# FADE.net
KiCad netlist of a schematic drawn in Altium Designer
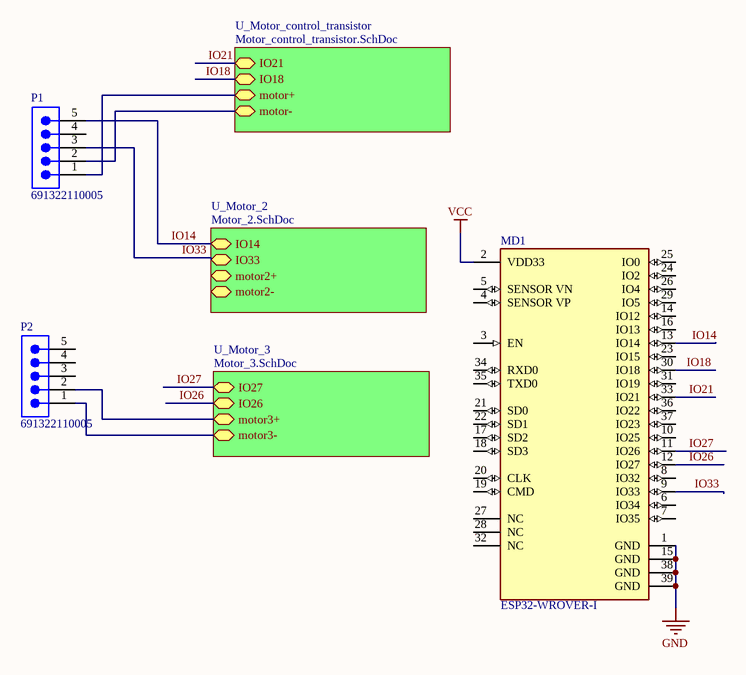
[diagram p0: FADE.SchDoc]

(export (version "E")
  (design (tool "Eeschema 10.0.6"))
  (components
    (comp (ref "MD1")
      (value "ESP32-WROVER-I")
      (footprint "FP-ESP32-WROVER-I-MFG")
      (description "SMD MODULE, ESP32-D0WDQ6, 32MBIT")
      (fields
        (field (name "MANUFACTURER") "Espressif")
        (field (name "OCTOPART") "https://octopart.com/esp32-wrover-i-espressif+systems-89171349")
      )
      (libsource (lib "Altium Content Vault") (part "cbbb37af8bcfe61dfd46ac9418f0340"))
    )
    (comp (ref "P1")
      (value "691322110005")
      (footprint "691322110005")
      (fields (field (name "VOLTAGE") "300V"))
      (libsource (lib "Altium Content Vault") (part "TBL - 1R - 05P - Male"))
    )
    (comp (ref "P2")
      (value "691322110005")
      (footprint "691322110005")
      (fields (field (name "VOLTAGE") "300V"))
      (libsource (lib "Altium Content Vault") (part "TBL - 1R - 05P - Male"))
    )
  )
  (nets
    (net (code "1") (name "/IO14") (class "Default")
      (node (ref "MD1") (pin "13") (pinfunction "IO14_13") (pintype "bidirectional"))
      (node (ref "P1") (pin "5") (pinfunction "5_5") (pintype "passive"))
    )
    (net (code "2") (name "/IO18") (class "Default")
      (node (ref "MD1") (pin "30") (pinfunction "IO18_30") (pintype "bidirectional"))
    )
    (net (code "3") (name "/IO21") (class "Default")
      (node (ref "MD1") (pin "33") (pinfunction "IO21_33") (pintype "bidirectional"))
    )
    (net (code "4") (name "/IO26") (class "Default")
      (node (ref "MD1") (pin "12") (pinfunction "IO27_12") (pintype "bidirectional"))
    )
    (net (code "5") (name "/IO27") (class "Default")
      (node (ref "MD1") (pin "11") (pinfunction "IO26_11") (pintype "bidirectional"))
    )
    (net (code "6") (name "/IO33") (class "Default")
      (node (ref "MD1") (pin "9") (pinfunction "IO33_9") (pintype "bidirectional"))
      (node (ref "P1") (pin "3") (pinfunction "3_3") (pintype "passive"))
    )
    (net (code "7") (name "/motor+") (class "Default")
      (node (ref "P1") (pin "1") (pinfunction "1_1") (pintype "passive"))
    )
    (net (code "8") (name "/motor-") (class "Default")
      (node (ref "P1") (pin "2") (pinfunction "2_2") (pintype "passive"))
    )
    (net (code "11") (name "/motor3+") (class "Default")
      (node (ref "P2") (pin "2") (pinfunction "2_2") (pintype "passive"))
    )
    (net (code "12") (name "/motor3-") (class "Default")
      (node (ref "P2") (pin "1") (pinfunction "1_1") (pintype "passive"))
    )
    (net (code "13") (name "GND") (class "Default")
      (node (ref "MD1") (pin "1") (pinfunction "GND_1") (pintype "power_in"))
      (node (ref "MD1") (pin "15") (pinfunction "GND_15") (pintype "power_in"))
      (node (ref "MD1") (pin "38") (pinfunction "GND_38") (pintype "power_in"))
      (node (ref "MD1") (pin "39") (pinfunction "GND_39") (pintype "power_in"))
    )
    (net (code "14") (name "VCC") (class "Default")
      (node (ref "MD1") (pin "2") (pinfunction "VDD33_2") (pintype "power_in"))
    )
    (net (code "15") (name "unconnected-(MD1-CLK-Pad20)") (class "Default")
      (node (ref "MD1") (pin "20") (pinfunction "CLK_20") (pintype "bidirectional"))
    )
    (net (code "16") (name "unconnected-(MD1-CMD-Pad19)") (class "Default")
      (node (ref "MD1") (pin "19") (pinfunction "CMD_19") (pintype "bidirectional"))
    )
    (net (code "17") (name "unconnected-(MD1-EN-Pad3)") (class "Default")
      (node (ref "MD1") (pin "3") (pinfunction "EN_3") (pintype "input"))
    )
    (net (code "18") (name "unconnected-(MD1-IO0-Pad25)") (class "Default")
      (node (ref "MD1") (pin "25") (pinfunction "IO0_25") (pintype "bidirectional"))
    )
    (net (code "19") (name "unconnected-(MD1-IO2-Pad24)") (class "Default")
      (node (ref "MD1") (pin "24") (pinfunction "IO2_24") (pintype "bidirectional"))
    )
    (net (code "20") (name "unconnected-(MD1-IO4-Pad26)") (class "Default")
      (node (ref "MD1") (pin "26") (pinfunction "IO4_26") (pintype "bidirectional"))
    )
    (net (code "21") (name "unconnected-(MD1-IO5-Pad29)") (class "Default")
      (node (ref "MD1") (pin "29") (pinfunction "IO5_29") (pintype "bidirectional"))
    )
    (net (code "22") (name "unconnected-(MD1-IO12-Pad14)") (class "Default")
      (node (ref "MD1") (pin "14") (pinfunction "IO12_14") (pintype "bidirectional"))
    )
    (net (code "23") (name "unconnected-(MD1-IO13-Pad16)") (class "Default")
      (node (ref "MD1") (pin "16") (pinfunction "IO13_16") (pintype "bidirectional"))
    )
    (net (code "24") (name "unconnected-(MD1-IO15-Pad23)") (class "Default")
      (node (ref "MD1") (pin "23") (pinfunction "IO15_23") (pintype "bidirectional"))
    )
    (net (code "25") (name "unconnected-(MD1-IO19-Pad31)") (class "Default")
      (node (ref "MD1") (pin "31") (pinfunction "IO19_31") (pintype "bidirectional"))
    )
    (net (code "26") (name "unconnected-(MD1-IO22-Pad36)") (class "Default")
      (node (ref "MD1") (pin "36") (pinfunction "IO22_36") (pintype "bidirectional"))
    )
    (net (code "27") (name "unconnected-(MD1-IO23-Pad37)") (class "Default")
      (node (ref "MD1") (pin "37") (pinfunction "IO23_37") (pintype "bidirectional"))
    )
    (net (code "28") (name "unconnected-(MD1-IO25-Pad10)") (class "Default")
      (node (ref "MD1") (pin "10") (pinfunction "IO25_10") (pintype "bidirectional"))
    )
    (net (code "29") (name "unconnected-(MD1-IO32-Pad8)") (class "Default")
      (node (ref "MD1") (pin "8") (pinfunction "IO32_8") (pintype "bidirectional"))
    )
    (net (code "30") (name "unconnected-(MD1-IO34-Pad6)") (class "Default")
      (node (ref "MD1") (pin "6") (pinfunction "IO34_6") (pintype "bidirectional"))
    )
    (net (code "31") (name "unconnected-(MD1-IO35-Pad7)") (class "Default")
      (node (ref "MD1") (pin "7") (pinfunction "IO35_7") (pintype "bidirectional"))
    )
    (net (code "32") (name "unconnected-(MD1-NC-Pad27)") (class "Default")
      (node (ref "MD1") (pin "27") (pinfunction "NC_27") (pintype "passive"))
    )
    (net (code "33") (name "unconnected-(MD1-NC-Pad28)") (class "Default")
      (node (ref "MD1") (pin "28") (pinfunction "NC_28") (pintype "passive"))
    )
    (net (code "34") (name "unconnected-(MD1-NC-Pad32)") (class "Default")
      (node (ref "MD1") (pin "32") (pinfunction "NC_32") (pintype "passive"))
    )
    (net (code "35") (name "unconnected-(MD1-RXD0-Pad34)") (class "Default")
      (node (ref "MD1") (pin "34") (pinfunction "RXD0_34") (pintype "bidirectional"))
    )
    (net (code "36") (name "unconnected-(MD1-SD0-Pad21)") (class "Default")
      (node (ref "MD1") (pin "21") (pinfunction "SD0_21") (pintype "bidirectional"))
    )
    (net (code "37") (name "unconnected-(MD1-SD1-Pad22)") (class "Default")
      (node (ref "MD1") (pin "22") (pinfunction "SD1_22") (pintype "bidirectional"))
    )
    (net (code "38") (name "unconnected-(MD1-SD2-Pad17)") (class "Default")
      (node (ref "MD1") (pin "17") (pinfunction "SD2_17") (pintype "bidirectional"))
    )
    (net (code "39") (name "unconnected-(MD1-SD3-Pad18)") (class "Default")
      (node (ref "MD1") (pin "18") (pinfunction "SD3_18") (pintype "bidirectional"))
    )
    (net (code "40") (name "unconnected-(MD1-SENSOR_VN-Pad5)") (class "Default")
      (node (ref "MD1") (pin "5") (pinfunction "SENSOR_VN_5") (pintype "bidirectional"))
    )
    (net (code "41") (name "unconnected-(MD1-SENSOR_VP-Pad4)") (class "Default")
      (node (ref "MD1") (pin "4") (pinfunction "SENSOR_VP_4") (pintype "bidirectional"))
    )
    (net (code "42") (name "unconnected-(MD1-TXD0-Pad35)") (class "Default")
      (node (ref "MD1") (pin "35") (pinfunction "TXD0_35") (pintype "bidirectional"))
    )
    (net (code "43") (name "unconnected-(P1-Pad4)") (class "Default")
      (node (ref "P1") (pin "4") (pinfunction "4_4") (pintype "passive"))
    )
    (net (code "44") (name "unconnected-(P2-Pad3)") (class "Default")
      (node (ref "P2") (pin "3") (pinfunction "3_3") (pintype "passive"))
    )
    (net (code "45") (name "unconnected-(P2-Pad4)") (class "Default")
      (node (ref "P2") (pin "4") (pinfunction "4_4") (pintype "passive"))
    )
    (net (code "46") (name "unconnected-(P2-Pad5)") (class "Default")
      (node (ref "P2") (pin "5") (pinfunction "5_5") (pintype "passive"))
    )
  )
)
